# Input_Power.net
KiCad netlist of a schematic drawn in Altium Designer
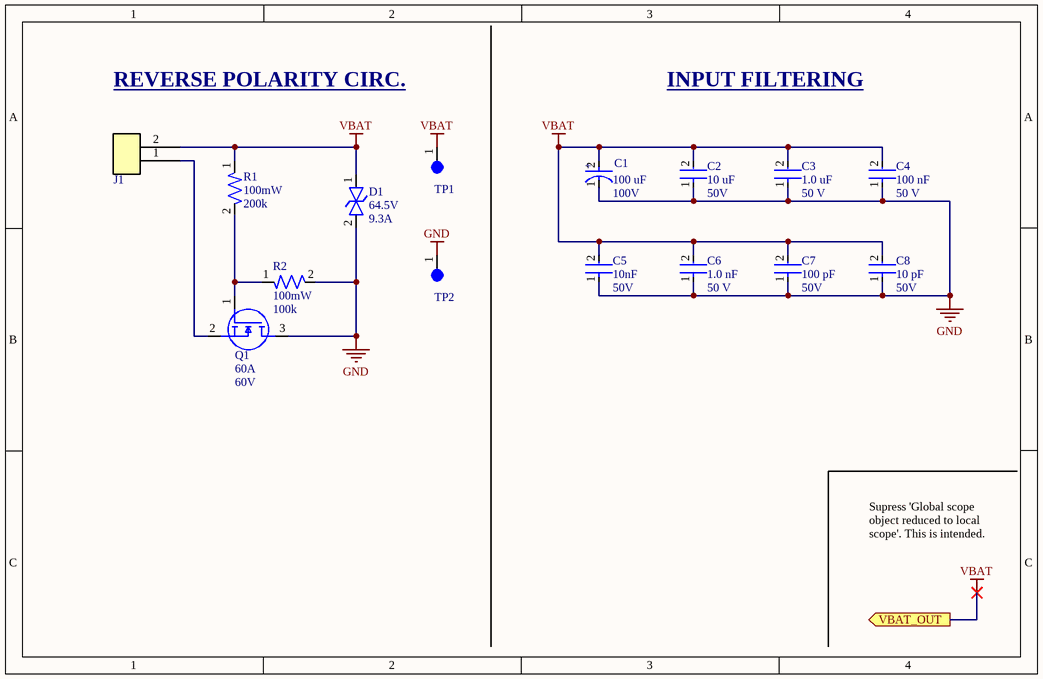
[diagram p0: Input_Power.SchDoc]

(export (version "E")
  (design (tool "Eeschema 10.0.6"))
  (components
    (comp (ref "C1")
      (value "EEETK2A101AM")
      (footprint "CAP-100U-0001")
      (description "CAP ALUM 100UF 20% 100V SMD")
      (fields (field (name "VOLTAGE") "100V") (field (name "CAPACITANCE") "100 uF"))
      (libsource (lib "JLC_25") (part "CAP-100U-0001"))
    )
    (comp (ref "C2")
      (value "CL32B106KBJNNNE")
      (footprint "CAP-1210")
      (description "CAP CER 10UF 50V X7R 1210")
      (fields (field (name "VOLTAGE") "50V") (field (name "CAPACITANCE") "10 uF"))
      (libsource (lib "JLC_25") (part "CAP-10U-0002"))
    )
    (comp (ref "C3")
      (value "CC0805KKX7R9BB105")
      (footprint "CAP-0805")
      (description "CAP CER 1UF 50V X7R 0805")
      (fields (field (name "VOLTAGE") "50 V") (field (name "CAPACITANCE") "1.0 uF"))
      (libsource (lib "JLC_25") (part "CAP-1U-0001"))
    )
    (comp (ref "C4")
      (value "CC0805KRX7R9BB104")
      (footprint "CAP-0805")
      (description "CAP CER 0.1UF 50V X7R 0805")
      (fields (field (name "VOLTAGE RATING") "50 V") (field (name "CAPACITANCE") "100 nF"))
      (libsource (lib "JLC_25") (part "CAP-0.1U-0002"))
    )
    (comp (ref "C5")
      (value "GRM2195C1H103JA01D")
      (footprint "CAP-0805")
      (description "CAP CER 10000PF 50V C0G/NP0 0805")
      (fields (field (name "VOLTAGE") "50V") (field (name "CAPACITANCE") "10nF"))
      (libsource (lib "JLC_25") (part "CAP-10N-0001"))
    )
    (comp (ref "C6")
      (value "CC0402KRX7R9BB102")
      (footprint "CAP-0402")
      (description "CAP CER 1000PF 50V X7R 0402")
      (fields (field (name "VOLTAGE") "50 V") (field (name "CAPACITANCE") "1.0 nF"))
      (libsource (lib "JLC_25") (part "CAP-1N-0001"))
    )
    (comp (ref "C7")
      (value "CC0402JRNPO9BN101")
      (footprint "CAP-0402")
      (description "CAP CER 100PF 50V C0G/NPO 0402")
      (fields (field (name "CAPACITANCE") "100 pF") (field (name "VOLTAGE") "50V"))
      (libsource (lib "JLC_25") (part "CAP-100P-0001"))
    )
    (comp (ref "C8")
      (value "CC0402JRNPO9BN100")
      (footprint "CAP-0402")
      (description "CAP CER 10PF 50V C0G/NPO 0402")
      (fields (field (name "CAPACITANCE") "10 pF") (field (name "VOLTAGE") "50V"))
      (libsource (lib "JLC_25") (part "CAP-10P-0001"))
    )
    (comp (ref "D1")
      (value "SMBJ40CA")
      (footprint "DO-214AA (SMBJ)")
      (description "TVS DIODE 40VWM 64.5VC DO214AA")
      (fields (field (name "VOLTAGE RATING") "64.5V") (field (name "CURRENT RATING") "9.3A"))
      (libsource (lib "JLC_25") (part "DIO-TVS-0001"))
    )
    (comp (ref "J1")
      (value "0436500215")
      (footprint "CONN-2POS-0002")
      (description "CONN HEADER VERT 2POS 3MM")
      (libsource (lib "JLC_25") (part "CONN-2POS-0002"))
    )
    (comp (ref "Q1")
      (value "CSD18543Q3AT")
      (footprint "IC-8VSONCLIP")
      (description "MOSFET N-CH 60V 12A/60A 8VSON")
      (fields (field (name "VOLTAGE") "60V") (field (name "CONTINUOUS CURRENT") "60A"))
      (libsource (lib "JLC_25") (part "NMOS-60A-0001"))
    )
    (comp (ref "R1")
      (value "RC0603FR-07200KL")
      (footprint "RES-0603")
      (description "RES SMD 200K OHM 1% 1/10W 0603")
      (fields
        (field (name "TOLERANCE") "1%")
        (field (name "POWER") "100mW")
        (field (name "RESISTANCE") "200k")
      )
      (libsource (lib "JLC_25") (part "RES-200k-0001"))
    )
    (comp (ref "R2")
      (value "RC0603FR-07100KL")
      (footprint "RES-0603")
      (description "RES SMD 100K OHM 1% 1/10W 0603")
      (fields
        (field (name "TOLERANCE") "1%")
        (field (name "POWER") "100mW")
        (field (name "RESISTANCE") "100k")
      )
      (libsource (lib "JLC_25") (part "RES-100k-0001"))
    )
    (comp (ref "TP1")
      (value "5003")
      (footprint "TEST-POINT-0001")
      (description "Oranange PC Test Point, Miniature Phoisphor Bronze Silver Plating Through Hole Mounting Type")
      (libsource (lib "*") (part "TEST-POINT-0001"))
    )
    (comp (ref "TP2")
      (value "5003")
      (footprint "TEST-POINT-0001")
      (description "Oranange PC Test Point, Miniature Phoisphor Bronze Silver Plating Through Hole Mounting Type")
      (libsource (lib "*") (part "TEST-POINT-0001"))
    )
  )
  (nets
    (net (code "1") (name "GND") (class "Default")
      (node (ref "C1") (pin "1") (pinfunction "2_1") (pintype "passive"))
      (node (ref "C2") (pin "1") (pinfunction "1_1") (pintype "passive"))
      (node (ref "C3") (pin "1") (pinfunction "1_1") (pintype "passive"))
      (node (ref "C4") (pin "1") (pinfunction "1_1") (pintype "passive"))
      (node (ref "C5") (pin "1") (pinfunction "1_1") (pintype "passive"))
      (node (ref "C6") (pin "1") (pinfunction "1_1") (pintype "passive"))
      (node (ref "C7") (pin "1") (pinfunction "1_1") (pintype "passive"))
      (node (ref "C8") (pin "1") (pinfunction "1_1") (pintype "passive"))
      (node (ref "D1") (pin "2") (pintype "passive"))
      (node (ref "Q1") (pin "3") (pinfunction "D_3") (pintype "passive"))
      (node (ref "R2") (pin "2") (pinfunction "2_2") (pintype "passive"))
      (node (ref "TP2") (pin "1") (pinfunction "0_1") (pintype "passive"))
    )
    (net (code "2") (name "Net-(J1-7)") (class "Default")
      (node (ref "J1") (pin "1") (pinfunction "7_1") (pintype "passive"))
      (node (ref "Q1") (pin "2") (pinfunction "S_2") (pintype "passive"))
    )
    (net (code "3") (name "Net-(Q1-G)") (class "Default")
      (node (ref "Q1") (pin "1") (pinfunction "G_1") (pintype "passive"))
      (node (ref "R1") (pin "2") (pinfunction "2_2") (pintype "passive"))
      (node (ref "R2") (pin "1") (pinfunction "1_1") (pintype "passive"))
    )
    (net (code "4") (name "VBAT") (class "Default")
      (node (ref "C1") (pin "2") (pinfunction "1_2") (pintype "passive"))
      (node (ref "C2") (pin "2") (pinfunction "2_2") (pintype "passive"))
      (node (ref "C3") (pin "2") (pinfunction "2_2") (pintype "passive"))
      (node (ref "C4") (pin "2") (pinfunction "2_2") (pintype "passive"))
      (node (ref "C5") (pin "2") (pinfunction "2_2") (pintype "passive"))
      (node (ref "C6") (pin "2") (pinfunction "2_2") (pintype "passive"))
      (node (ref "C7") (pin "2") (pinfunction "2_2") (pintype "passive"))
      (node (ref "C8") (pin "2") (pinfunction "2_2") (pintype "passive"))
      (node (ref "D1") (pin "1") (pintype "passive"))
      (node (ref "J1") (pin "2") (pinfunction "8_2") (pintype "passive"))
      (node (ref "R1") (pin "1") (pinfunction "1_1") (pintype "passive"))
      (node (ref "TP1") (pin "1") (pinfunction "0_1") (pintype "passive"))
    )
  )
)
